# LPS.net
KiCad netlist of a schematic drawn in Altium Designer
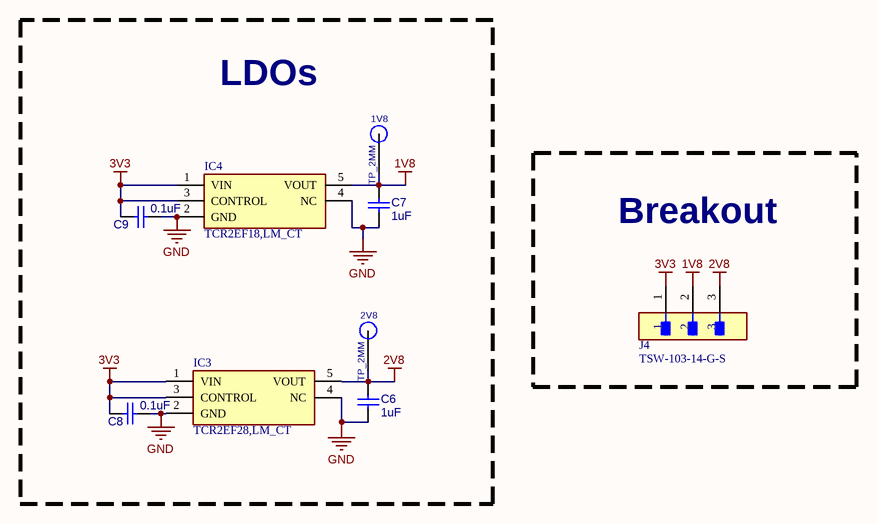
[diagram p0: LPS.SchDoc]

(export (version "E")
  (design (tool "Eeschema 10.0.6"))
  (components
    (comp (ref "1V8") (value "TP_2MM") (footprint "TESTPOINT 2MM") (libsource (lib "C2S") (part "TP_2MM")))
    (comp (ref "2V8") (value "TP_2MM") (footprint "TESTPOINT 2MM") (libsource (lib "C2S") (part "TP_2MM")))
    (comp (ref "C6")
      (value "1uF")
      (footprint "C0603")
      (description "Capacitor, MLCC, 100nF, 6V3, X5R, 10%, 0603, T=0,8mm")
      (fields
        (field (name "MANUFACTURER PART NUMBER") "CC0603KRX5R5BB104")
        (field (name "MANUFACTURER") "YAGEO")
        (field (name "PROVIDED_BY") "SUBCO")
      )
      (libsource (lib "Perth Aerospace Student Team") (part "CMP-035-000015-1"))
    )
    (comp (ref "C7")
      (value "1uF")
      (footprint "C0603")
      (description "Capacitor, MLCC, 100nF, 6V3, X5R, 10%, 0603, T=0,8mm")
      (fields
        (field (name "MANUFACTURER PART NUMBER") "CC0603KRX5R5BB104")
        (field (name "MANUFACTURER") "YAGEO")
        (field (name "PROVIDED_BY") "SUBCO")
      )
      (libsource (lib "Perth Aerospace Student Team") (part "CMP-035-000015-1"))
    )
    (comp (ref "C8")
      (value "0.1uF")
      (footprint "C0603")
      (description "Capacitor, MLCC, 100nF, 6V3, X5R, 10%, 0603, T=0,8mm")
      (fields
        (field (name "MANUFACTURER PART NUMBER") "CC0603KRX5R5BB104")
        (field (name "MANUFACTURER") "YAGEO")
        (field (name "PROVIDED_BY") "SUBCO")
      )
      (libsource (lib "Perth Aerospace Student Team") (part "CMP-035-000015-1"))
    )
    (comp (ref "C9")
      (value "0.1uF")
      (footprint "C0603")
      (description "Capacitor, MLCC, 100nF, 6V3, X5R, 10%, 0603, T=0,8mm")
      (fields
        (field (name "MANUFACTURER PART NUMBER") "CC0603KRX5R5BB104")
        (field (name "MANUFACTURER") "YAGEO")
        (field (name "PROVIDED_BY") "SUBCO")
      )
      (libsource (lib "Perth Aerospace Student Team") (part "CMP-035-000015-1"))
    )
    (comp (ref "IC3")
      (value "TCR2EF28,LM_CT")
      (footprint "C2Sv0.1:TCR2EF28LMCT")
      (description "Integrated Circuit")
      (fields
        (field (name "MANUFACTURER_PART_NUMBER") "TCR2EF28,LM(CT")
        (field (name "MOUSER PART NUMBER") "757-TCR2EF28LMCT")
      )
      (libsource (lib "C2Sv0.1") (part "TCR2EF28,LM_CT"))
    )
    (comp (ref "IC4")
      (value "TCR2EF18,LM_CT")
      (footprint "C2Sv0.1:TCR2EF18LMCT")
      (description "Integrated Circuit")
      (fields
        (field (name "MANUFACTURER_PART_NUMBER") "TCR2EF18,LM(CT")
        (field (name "MOUSER PART NUMBER") "757-TCR2EF18LMCT")
      )
      (libsource (lib "C2Sv0.1") (part "TCR2EF18,LM_CT"))
    )
    (comp (ref "J4")
      (value "TSW-103-14-G-S")
      (footprint "FP-TSW-103-14-G-S-MFG")
      (description "CONN HEADER VERT 3POS 2.54MM")
      (libsource (lib "Altium Content Vault") (part "cd3439d6ef35ae5d9b27ec4fdd3e828"))
    )
  )
  (nets
    (net (code "1") (name "1V8") (class "Default")
      (node (ref "1V8") (pin "TP") (pinfunction "TP_2MM_TP") (pintype "passive"))
      (node (ref "C7") (pin "1") (pinfunction "1_1") (pintype "passive"))
      (node (ref "IC4") (pin "5") (pinfunction "VOUT_5") (pintype "passive"))
      (node (ref "J4") (pin "2") (pinfunction "2_2") (pintype "passive"))
    )
    (net (code "2") (name "2V8") (class "Default")
      (node (ref "2V8") (pin "TP") (pinfunction "TP_2MM_TP") (pintype "passive"))
      (node (ref "C6") (pin "1") (pinfunction "1_1") (pintype "passive"))
      (node (ref "IC3") (pin "5") (pinfunction "VOUT_5") (pintype "passive"))
      (node (ref "J4") (pin "3") (pinfunction "3_3") (pintype "passive"))
    )
    (net (code "3") (name "3V3") (class "Default")
      (node (ref "C8") (pin "2") (pinfunction "2_2") (pintype "passive"))
      (node (ref "C9") (pin "2") (pinfunction "2_2") (pintype "passive"))
      (node (ref "IC3") (pin "1") (pinfunction "VIN_1") (pintype "passive"))
      (node (ref "IC3") (pin "3") (pinfunction "CONTROL_3") (pintype "passive"))
      (node (ref "IC4") (pin "1") (pinfunction "VIN_1") (pintype "passive"))
      (node (ref "IC4") (pin "3") (pinfunction "CONTROL_3") (pintype "passive"))
      (node (ref "J4") (pin "1") (pinfunction "1_1") (pintype "passive"))
    )
    (net (code "4") (name "GND") (class "Default")
      (node (ref "C6") (pin "2") (pinfunction "2_2") (pintype "passive"))
      (node (ref "C7") (pin "2") (pinfunction "2_2") (pintype "passive"))
      (node (ref "C8") (pin "1") (pinfunction "1_1") (pintype "passive"))
      (node (ref "C9") (pin "1") (pinfunction "1_1") (pintype "passive"))
      (node (ref "IC3") (pin "2") (pinfunction "GND_2") (pintype "passive"))
      (node (ref "IC3") (pin "4") (pinfunction "NC_4") (pintype "passive"))
      (node (ref "IC4") (pin "2") (pinfunction "GND_2") (pintype "passive"))
      (node (ref "IC4") (pin "4") (pinfunction "NC_4") (pintype "passive"))
    )
  )
)
